# foxcar-control-board-v1.net
KiCad netlist of a schematic drawn in EAGLE
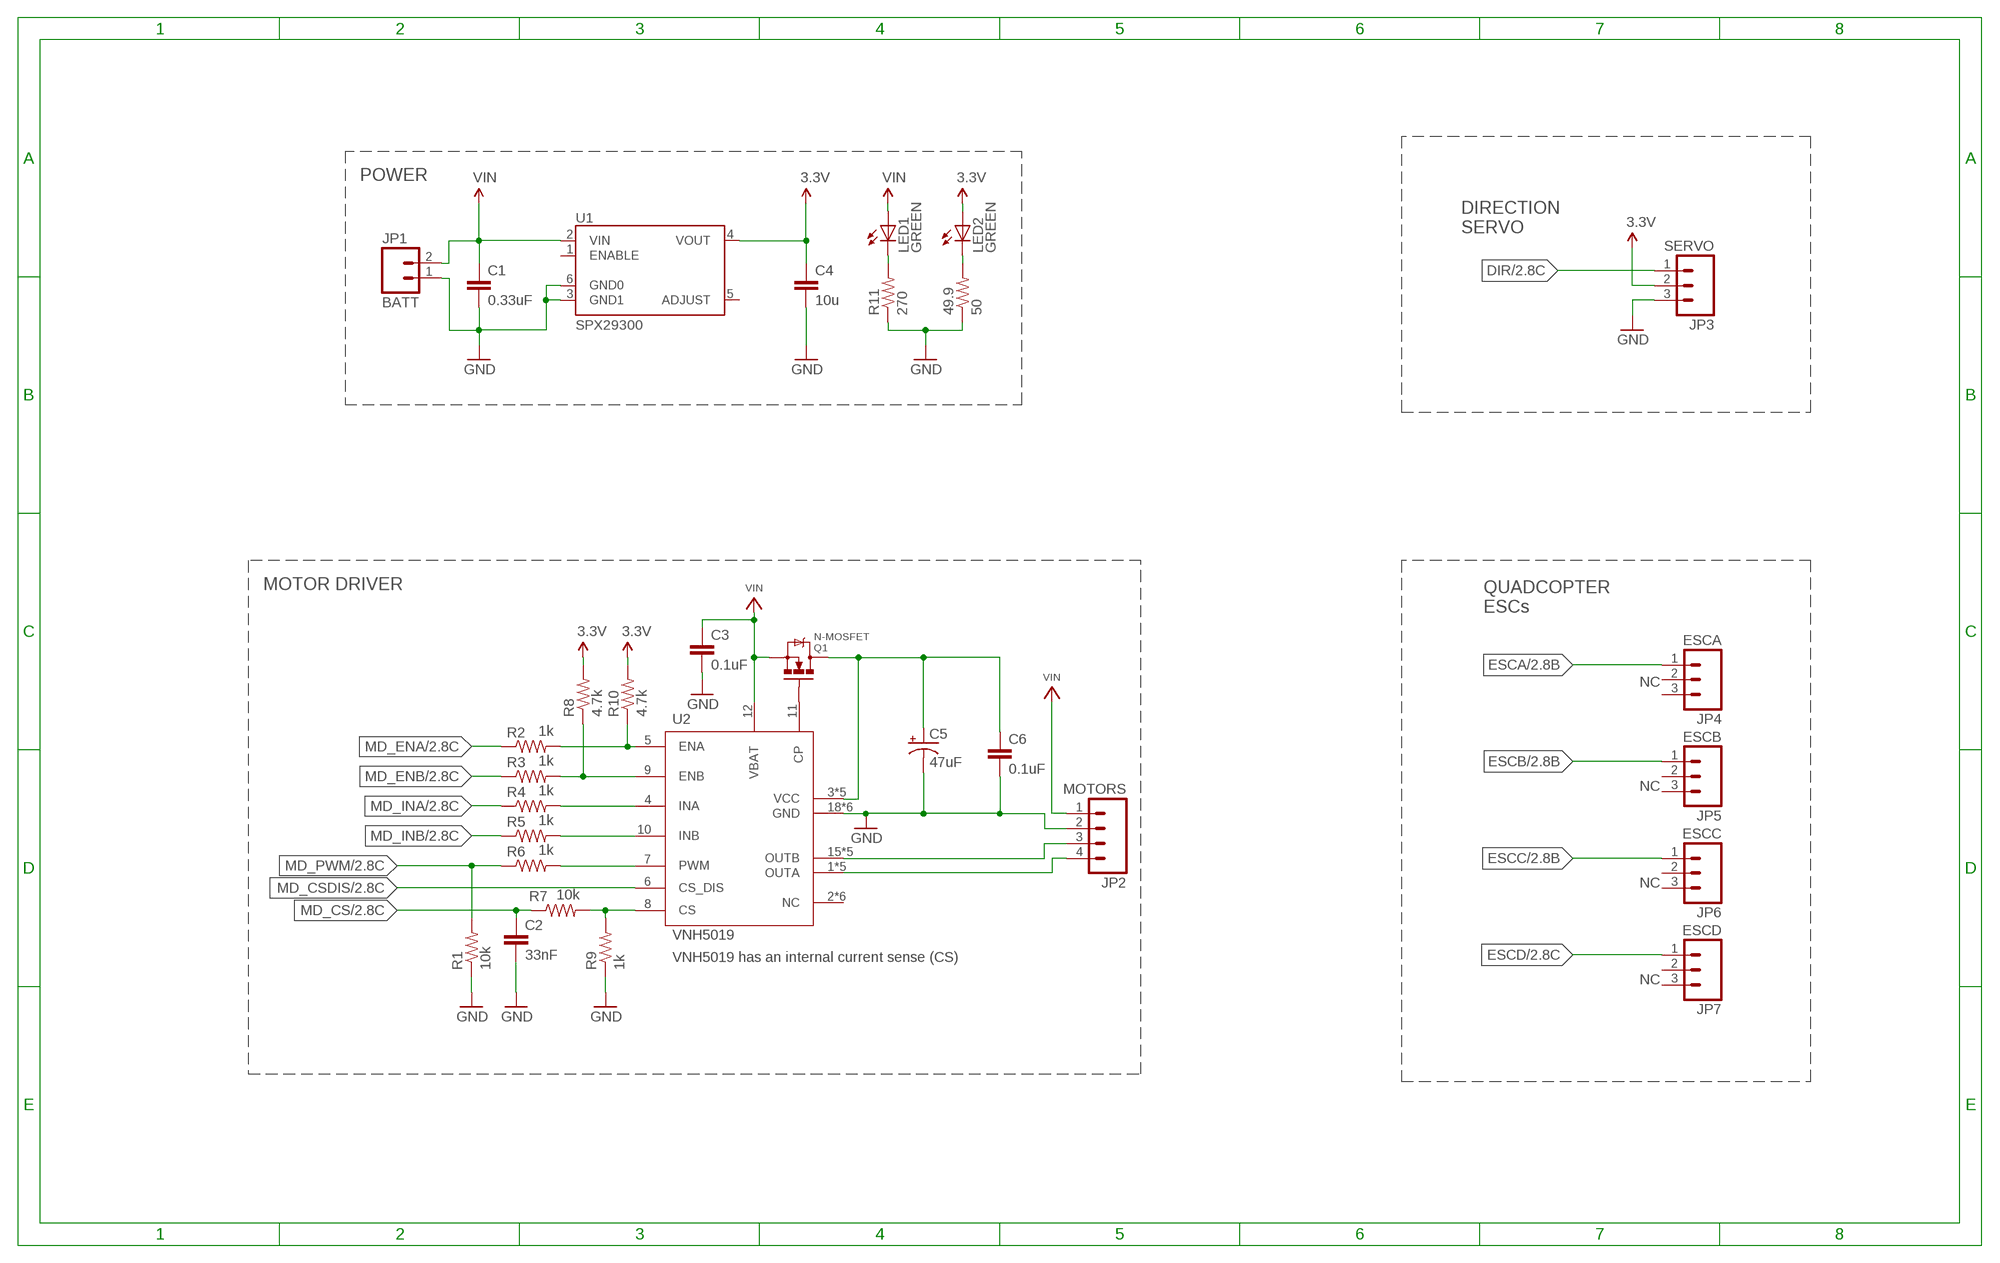
[diagram p0: schematic, sheet 1]
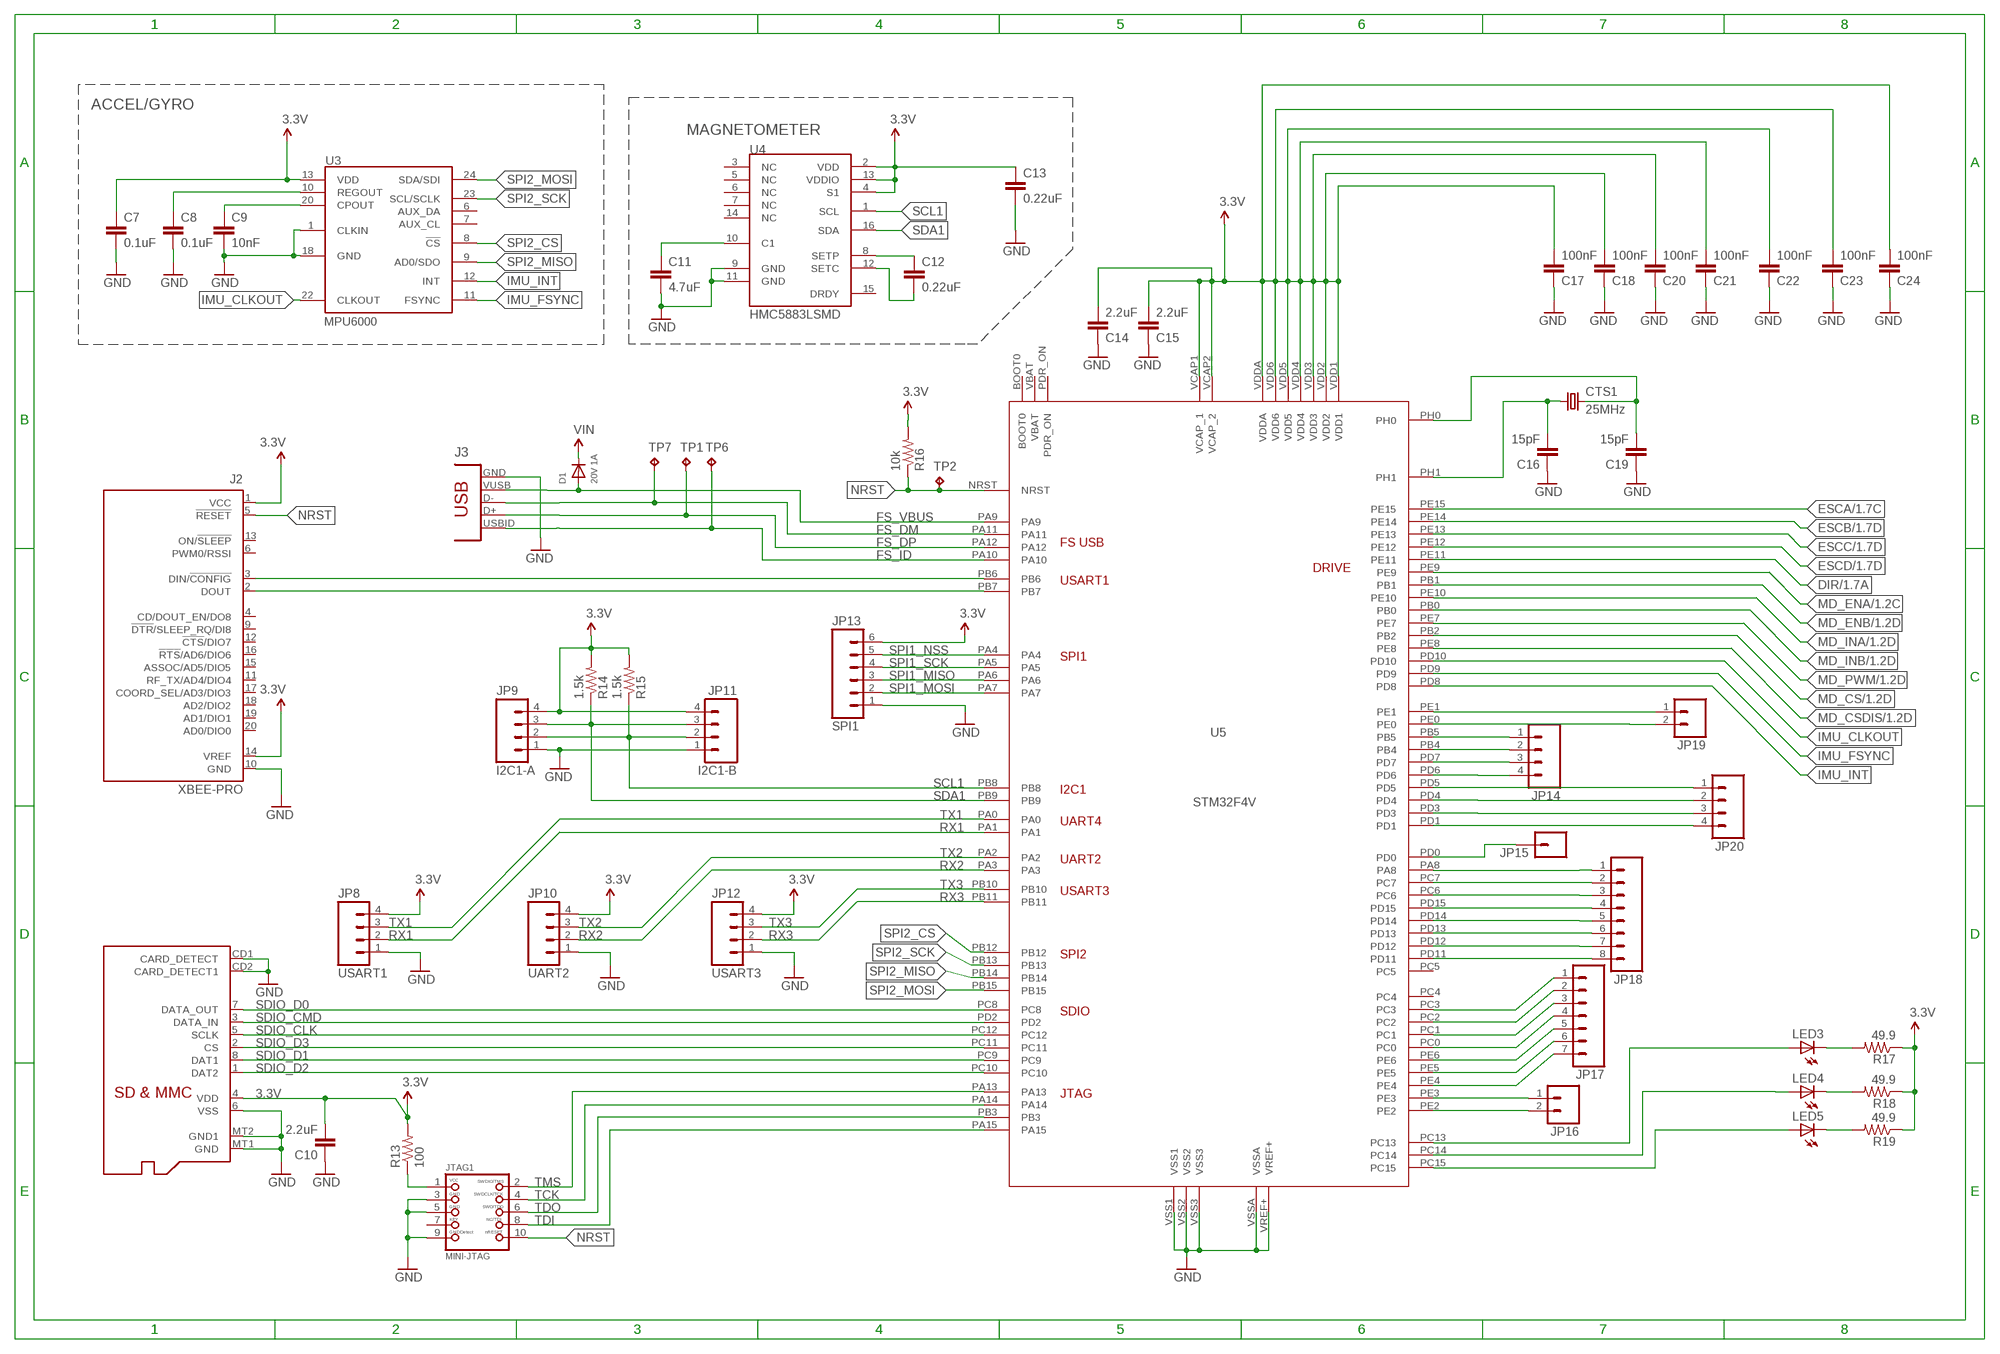
[diagram p1: schematic, sheet 2]

(export (version "E")
  (design (tool "Eeschema 10.0.6"))
  (components
    (comp (ref "C7")
      (value "0.1uF")
      (footprint "eagle-import:0402-CAP")
      (libsource (lib "eagle-import") (part "CAP0402-CAP"))
    )
    (comp (ref "C8")
      (value "0.1uF")
      (footprint "eagle-import:0402-CAP")
      (libsource (lib "eagle-import") (part "CAP0402-CAP"))
    )
    (comp (ref "C9")
      (value "10nF")
      (footprint "eagle-import:0402-CAP")
      (libsource (lib "eagle-import") (part "CAP0402-CAP"))
    )
    (comp (ref "C10")
      (value "2.2uF")
      (footprint "eagle-import:0402-CAP")
      (libsource (lib "eagle-import") (part "CAP0402-CAP"))
    )
    (comp (ref "C11")
      (value "4.7uF")
      (footprint "eagle-import:0402-CAP")
      (libsource (lib "eagle-import") (part "CAP0402-CAP"))
    )
    (comp (ref "C12")
      (value "0.22uF")
      (footprint "eagle-import:0402-CAP")
      (libsource (lib "eagle-import") (part "CAP0402-CAP"))
    )
    (comp (ref "C13")
      (value "0.22uF")
      (footprint "eagle-import:0402-CAP")
      (libsource (lib "eagle-import") (part "CAP0402-CAP"))
    )
    (comp (ref "C14")
      (value "2.2uF")
      (footprint "eagle-import:0402-CAP")
      (libsource (lib "eagle-import") (part "CAP0402-CAP"))
    )
    (comp (ref "C15")
      (value "2.2uF")
      (footprint "eagle-import:0402-CAP")
      (libsource (lib "eagle-import") (part "CAP0402-CAP"))
    )
    (comp (ref "C16")
      (value "15pF")
      (footprint "eagle-import:0402-CAP")
      (libsource (lib "eagle-import") (part "CAP0402-CAP"))
    )
    (comp (ref "C17")
      (value "100nF")
      (footprint "eagle-import:0402-CAP")
      (libsource (lib "eagle-import") (part "CAP0402-CAP"))
    )
    (comp (ref "C18")
      (value "100nF")
      (footprint "eagle-import:0402-CAP")
      (libsource (lib "eagle-import") (part "CAP0402-CAP"))
    )
    (comp (ref "C19")
      (value "15pF")
      (footprint "eagle-import:0402-CAP")
      (libsource (lib "eagle-import") (part "CAP0402-CAP"))
    )
    (comp (ref "C20")
      (value "100nF")
      (footprint "eagle-import:0402-CAP")
      (libsource (lib "eagle-import") (part "CAP0402-CAP"))
    )
    (comp (ref "C21")
      (value "100nF")
      (footprint "eagle-import:0402-CAP")
      (libsource (lib "eagle-import") (part "CAP0402-CAP"))
    )
    (comp (ref "C22")
      (value "100nF")
      (footprint "eagle-import:0402-CAP")
      (libsource (lib "eagle-import") (part "CAP0402-CAP"))
    )
    (comp (ref "C23")
      (value "100nF")
      (footprint "eagle-import:0402-CAP")
      (libsource (lib "eagle-import") (part "CAP0402-CAP"))
    )
    (comp (ref "C24")
      (value "100nF")
      (footprint "eagle-import:0402-CAP")
      (libsource (lib "eagle-import") (part "CAP0402-CAP"))
    )
    (comp (ref "CTS1")
      (value "25MHz")
      (footprint "eagle-import:CTS406")
      (libsource (lib "eagle-import") (part "CRYSTALCTS406"))
    )
    (comp (ref "D1")
      (value "20V 1A")
      (footprint "eagle-import:SMADIODE")
      (libsource (lib "eagle-import") (part "DIODESMA"))
    )
    (comp (ref "J1")
      (value "MICROSD")
      (footprint "eagle-import:MICROSD")
      (libsource (lib "eagle-import") (part "MICROSD"))
    )
    (comp (ref "J2")
      (value "XBEE-PRO")
      (footprint "eagle-import:XBEE-PRO")
      (fields (field (name "MPN") "XBP24-AWI-001"))
      (libsource (lib "eagle-import") (part "XBEE-PRO"))
    )
    (comp (ref "J3")
      (value "CON-USB-F-MICRO-B")
      (footprint "eagle-import:CONN_USB_MICRO-B")
      (libsource (lib "eagle-import") (part "CON-USB-F-MICRO-B"))
    )
    (comp (ref "JP8")
      (value "USART1")
      (footprint "eagle-import:1X04_LOCK_LONGPADS")
      (libsource (lib "eagle-import") (part "M04LOCK_LONGPADS"))
    )
    (comp (ref "JP9")
      (value "I2C1-A")
      (footprint "eagle-import:1X04_LOCK_LONGPADS")
      (libsource (lib "eagle-import") (part "M04LOCK_LONGPADS"))
    )
    (comp (ref "JP10")
      (value "UART2")
      (footprint "eagle-import:1X04_LOCK_LONGPADS")
      (libsource (lib "eagle-import") (part "M04LOCK_LONGPADS"))
    )
    (comp (ref "JP11")
      (value "I2C1-B")
      (footprint "eagle-import:1X04_LOCK_LONGPADS")
      (libsource (lib "eagle-import") (part "M04LOCK_LONGPADS"))
    )
    (comp (ref "JP12")
      (value "USART3")
      (footprint "eagle-import:1X04_LOCK_LONGPADS")
      (libsource (lib "eagle-import") (part "M04LOCK_LONGPADS"))
    )
    (comp (ref "JP13")
      (value "SPI1")
      (footprint "eagle-import:1X06_LOCK_LONGPADS")
      (libsource (lib "eagle-import") (part "M06LOCK_LONGPADS"))
    )
    (comp (ref "JP14")
      (value "M04LOCK")
      (footprint "eagle-import:1X04_LOCK")
      (libsource (lib "eagle-import") (part "M04LOCK"))
    )
    (comp (ref "JP15")
      (value "M01PTH")
      (footprint "eagle-import:1X01")
      (libsource (lib "eagle-import") (part "M01PTH"))
    )
    (comp (ref "JP16")
      (value "M02LOCK_LONGPADS")
      (footprint "eagle-import:1X02_LOCK_LONGPADS")
      (libsource (lib "eagle-import") (part "M02LOCK_LONGPADS"))
    )
    (comp (ref "JP17")
      (value "M07LOCK")
      (footprint "eagle-import:1X07_LOCK")
      (libsource (lib "eagle-import") (part "M07LOCK"))
    )
    (comp (ref "JP18")
      (value "M08LOCK_LONGPADS")
      (footprint "eagle-import:1X08_LOCK_LONGPADS")
      (libsource (lib "eagle-import") (part "M08LOCK_LONGPADS"))
    )
    (comp (ref "JP19")
      (value "M02LOCK")
      (footprint "eagle-import:1X02_LOCK")
      (libsource (lib "eagle-import") (part "M02LOCK"))
    )
    (comp (ref "JP20")
      (value "M04LOCK")
      (footprint "eagle-import:1X04_LOCK")
      (libsource (lib "eagle-import") (part "M04LOCK"))
    )
    (comp (ref "JTAG1")
      (value "MINI-JTAG")
      (footprint "eagle-import:2X05_1.27MM_SMT")
      (libsource (lib "eagle-import") (part "JTAG-CORTEXM3"))
    )
    (comp (ref "LED3")
      (value "LEDCHIPLED_0603")
      (footprint "eagle-import:CHIPLED_0603")
      (libsource (lib "eagle-import") (part "LEDCHIPLED_0603"))
    )
    (comp (ref "LED4")
      (value "LEDCHIPLED_0603")
      (footprint "eagle-import:CHIPLED_0603")
      (libsource (lib "eagle-import") (part "LEDCHIPLED_0603"))
    )
    (comp (ref "LED5")
      (value "LEDCHIPLED_0603")
      (footprint "eagle-import:CHIPLED_0603")
      (libsource (lib "eagle-import") (part "LEDCHIPLED_0603"))
    )
    (comp (ref "R13")
      (value "100")
      (footprint "eagle-import:0402-RES")
      (libsource (lib "eagle-import") (part "RESISTOR0402-RES"))
    )
    (comp (ref "R14")
      (value "1.5k")
      (footprint "eagle-import:0402-RES")
      (libsource (lib "eagle-import") (part "RESISTOR0402-RES"))
    )
    (comp (ref "R15")
      (value "1.5k")
      (footprint "eagle-import:0402-RES")
      (libsource (lib "eagle-import") (part "RESISTOR0402-RES"))
    )
    (comp (ref "R16")
      (value "10k")
      (footprint "eagle-import:0402-RES")
      (libsource (lib "eagle-import") (part "RESISTOR0402-RES"))
    )
    (comp (ref "R17")
      (value "49.9")
      (footprint "eagle-import:0402-RES")
      (libsource (lib "eagle-import") (part "RESISTOR0402-RES"))
    )
    (comp (ref "R18")
      (value "49.9")
      (footprint "eagle-import:0402-RES")
      (libsource (lib "eagle-import") (part "RESISTOR0402-RES"))
    )
    (comp (ref "R19")
      (value "49.9")
      (footprint "eagle-import:0402-RES")
      (libsource (lib "eagle-import") (part "RESISTOR0402-RES"))
    )
    (comp (ref "TP1")
      (value "TPTP06R")
      (footprint "eagle-import:TP06R")
      (libsource (lib "eagle-import") (part "TPTP06R"))
    )
    (comp (ref "TP2")
      (value "TPTP06R")
      (footprint "eagle-import:TP06R")
      (libsource (lib "eagle-import") (part "TPTP06R"))
    )
    (comp (ref "TP6")
      (value "TPTP06R")
      (footprint "eagle-import:TP06R")
      (libsource (lib "eagle-import") (part "TPTP06R"))
    )
    (comp (ref "TP7")
      (value "TPTP06R")
      (footprint "eagle-import:TP06R")
      (libsource (lib "eagle-import") (part "TPTP06R"))
    )
    (comp (ref "U3")
      (value "MPU6000")
      (footprint "eagle-import:QFN.24.4X4")
      (libsource (lib "eagle-import") (part "MPU-6000"))
    )
    (comp (ref "U4")
      (value "HMC5883LSMD")
      (footprint "eagle-import:16LPCC")
      (libsource (lib "eagle-import") (part "HMC5883LSMD"))
    )
    (comp (ref "U5")
      (value "STM32F4V")
      (footprint "eagle-import:LQFP100")
      (libsource (lib "eagle-import") (part "STM32F4V_100PIN_FOXCAR"))
    )
    (comp (ref "49.9")
      (value "50")
      (footprint "eagle-import:0402-RES")
      (libsource (lib "eagle-import") (part "RESISTOR0402-RES"))
    )
    (comp (ref "C1")
      (value "0.33uF")
      (footprint "eagle-import:0402-CAP")
      (libsource (lib "eagle-import") (part "CAP0402-CAP"))
    )
    (comp (ref "C2")
      (value "33nF")
      (footprint "eagle-import:0402-CAP")
      (libsource (lib "eagle-import") (part "CAP0402-CAP"))
    )
    (comp (ref "C3")
      (value "0.1uF")
      (footprint "eagle-import:0402-CAP")
      (libsource (lib "eagle-import") (part "CAP0402-CAP"))
    )
    (comp (ref "C4")
      (value "10u")
      (footprint "eagle-import:0603-CAP")
      (libsource (lib "eagle-import") (part "CAP0603-CAP"))
    )
    (comp (ref "C5")
      (value "47uF")
      (footprint "eagle-import:PANASONIC_D")
      (libsource (lib "eagle-import") (part "CAP_POLD"))
    )
    (comp (ref "C6")
      (value "0.1uF")
      (footprint "eagle-import:0402-CAP")
      (libsource (lib "eagle-import") (part "CAP0402-CAP"))
    )
    (comp (ref "JP1")
      (value "BATT")
      (footprint "eagle-import:SCREWTERMINAL-3.5MM-2_LOCK")
      (libsource (lib "eagle-import") (part "M023.5MM_LOCK"))
    )
    (comp (ref "JP2")
      (value "MOTORS")
      (footprint "eagle-import:SCREWTERMINAL-3.5MM-4_LOCK")
      (libsource (lib "eagle-import") (part "M04SCREW_LOCK"))
    )
    (comp (ref "JP3")
      (value "SERVO")
      (footprint "eagle-import:1X03_LOCK_LONGPADS")
      (libsource (lib "eagle-import") (part "M03LOCK_LONGPADS"))
    )
    (comp (ref "JP4")
      (value "ESCA")
      (footprint "eagle-import:1X03_LOCK_LONGPADS")
      (libsource (lib "eagle-import") (part "M03LOCK_LONGPADS"))
    )
    (comp (ref "JP5")
      (value "ESCB")
      (footprint "eagle-import:1X03_LOCK_LONGPADS")
      (libsource (lib "eagle-import") (part "M03LOCK_LONGPADS"))
    )
    (comp (ref "JP6")
      (value "ESCC")
      (footprint "eagle-import:1X03_LOCK_LONGPADS")
      (libsource (lib "eagle-import") (part "M03LOCK_LONGPADS"))
    )
    (comp (ref "JP7")
      (value "ESCD")
      (footprint "eagle-import:1X03_LOCK_LONGPADS")
      (libsource (lib "eagle-import") (part "M03LOCK_LONGPADS"))
    )
    (comp (ref "LED1")
      (value "GREEN")
      (footprint "eagle-import:CHIPLED_0603")
      (libsource (lib "eagle-import") (part "LEDCHIPLED_0603"))
    )
    (comp (ref "LED2")
      (value "GREEN")
      (footprint "eagle-import:CHIPLED_0603")
      (libsource (lib "eagle-import") (part "LEDCHIPLED_0603"))
    )
    (comp (ref "Q1")
      (value "N-MOSFET")
      (footprint "eagle-import:TO220V")
      (libsource (lib "eagle-import") (part "MOSFET-NCHANNELPTH2"))
    )
    (comp (ref "R1")
      (value "10k")
      (footprint "eagle-import:0603-RES")
      (libsource (lib "eagle-import") (part "RESISTOR0603-RES"))
    )
    (comp (ref "R2")
      (value "1k")
      (footprint "eagle-import:0402-RES")
      (libsource (lib "eagle-import") (part "RESISTOR0402-RES"))
    )
    (comp (ref "R3")
      (value "1k")
      (footprint "eagle-import:0402-RES")
      (libsource (lib "eagle-import") (part "RESISTOR0402-RES"))
    )
    (comp (ref "R4")
      (value "1k")
      (footprint "eagle-import:0402-RES")
      (libsource (lib "eagle-import") (part "RESISTOR0402-RES"))
    )
    (comp (ref "R5")
      (value "1k")
      (footprint "eagle-import:0402-RES")
      (libsource (lib "eagle-import") (part "RESISTOR0402-RES"))
    )
    (comp (ref "R6")
      (value "1k")
      (footprint "eagle-import:0402-RES")
      (libsource (lib "eagle-import") (part "RESISTOR0402-RES"))
    )
    (comp (ref "R7")
      (value "10k")
      (footprint "eagle-import:0402-RES")
      (libsource (lib "eagle-import") (part "RESISTOR0402-RES"))
    )
    (comp (ref "R8")
      (value "4.7k")
      (footprint "eagle-import:0402-RES")
      (libsource (lib "eagle-import") (part "RESISTOR0402-RES"))
    )
    (comp (ref "R9")
      (value "1k")
      (footprint "eagle-import:0402-RES")
      (libsource (lib "eagle-import") (part "RESISTOR0402-RES"))
    )
    (comp (ref "R10")
      (value "4.7k")
      (footprint "eagle-import:0402-RES")
      (libsource (lib "eagle-import") (part "RESISTOR0402-RES"))
    )
    (comp (ref "R11")
      (value "270")
      (footprint "eagle-import:0603-RES")
      (libsource (lib "eagle-import") (part "RESISTOR0603-RES"))
    )
    (comp (ref "U1")
      (value "SPX29300")
      (footprint "eagle-import:TO263-5")
      (libsource (lib "eagle-import") (part "VREG_TO263-5"))
    )
    (comp (ref "U2")
      (value "VNH5019")
      (footprint "eagle-import:MULTIPOWERSO-30")
      (libsource (lib "eagle-import") (part "VNH5019"))
    )
  )
  (nets
    (net (code "1") (name "3.3V") (class "Default")
      (node (ref "C10") (pin "2") (pinfunction "2_2") (pintype "passive"))
      (node (ref "C13") (pin "1") (pinfunction "1_1") (pintype "passive"))
      (node (ref "C14") (pin "2") (pinfunction "2_2") (pintype "passive"))
      (node (ref "C15") (pin "2") (pinfunction "2_2") (pintype "passive"))
      (node (ref "C17") (pin "2") (pinfunction "2_2") (pintype "passive"))
      (node (ref "C18") (pin "2") (pinfunction "2_2") (pintype "passive"))
      (node (ref "C20") (pin "2") (pinfunction "2_2") (pintype "passive"))
      (node (ref "C21") (pin "2") (pinfunction "2_2") (pintype "passive"))
      (node (ref "C22") (pin "2") (pinfunction "2_2") (pintype "passive"))
      (node (ref "C23") (pin "2") (pinfunction "2_2") (pintype "passive"))
      (node (ref "C24") (pin "2") (pinfunction "2_2") (pintype "passive"))
      (node (ref "C4") (pin "1") (pinfunction "1_1") (pintype "passive"))
      (node (ref "C7") (pin "1") (pinfunction "1_1") (pintype "passive"))
      (node (ref "J1") (pin "4") (pinfunction "VDD_4") (pintype "power_in"))
      (node (ref "J2") (pin "1") (pinfunction "VCC_1") (pintype "power_in"))
      (node (ref "J2") (pin "14") (pinfunction "VREF_14") (pintype "input"))
      (node (ref "JP10") (pin "4") (pinfunction "4_4") (pintype "passive"))
      (node (ref "JP11") (pin "4") (pinfunction "4_4") (pintype "passive"))
      (node (ref "JP12") (pin "4") (pinfunction "4_4") (pintype "passive"))
      (node (ref "JP13") (pin "6") (pinfunction "6_6") (pintype "passive"))
      (node (ref "JP3") (pin "2") (pinfunction "2_2") (pintype "passive"))
      (node (ref "JP8") (pin "4") (pinfunction "4_4") (pintype "passive"))
      (node (ref "JP9") (pin "4") (pinfunction "4_4") (pintype "passive"))
      (node (ref "LED2") (pin "A") (pinfunction "A_A") (pintype "passive"))
      (node (ref "R10") (pin "2") (pinfunction "2_2") (pintype "passive"))
      (node (ref "R13") (pin "2") (pinfunction "2_2") (pintype "passive"))
      (node (ref "R14") (pin "2") (pinfunction "2_2") (pintype "passive"))
      (node (ref "R15") (pin "2") (pinfunction "2_2") (pintype "passive"))
      (node (ref "R16") (pin "2") (pinfunction "2_2") (pintype "passive"))
      (node (ref "R17") (pin "1") (pinfunction "1_1") (pintype "passive"))
      (node (ref "R18") (pin "1") (pinfunction "1_1") (pintype "passive"))
      (node (ref "R19") (pin "1") (pinfunction "1_1") (pintype "passive"))
      (node (ref "R8") (pin "2") (pinfunction "2_2") (pintype "passive"))
      (node (ref "U1") (pin "4") (pinfunction "VOUT_4") (pintype "bidirectional"))
      (node (ref "U3") (pin "13") (pinfunction "VDD_13") (pintype "bidirectional"))
      (node (ref "U4") (pin "13") (pinfunction "VDDIO_13") (pintype "bidirectional"))
      (node (ref "U4") (pin "2") (pinfunction "VDD_2") (pintype "bidirectional"))
      (node (ref "U4") (pin "4") (pinfunction "S1_4") (pintype "bidirectional"))
      (node (ref "U5") (pin "VCAP1") (pinfunction "VCAP_1_VCAP1") (pintype "bidirectional"))
      (node (ref "U5") (pin "VCAP2") (pinfunction "VCAP_2_VCAP2") (pintype "bidirectional"))
      (node (ref "U5") (pin "VDD1") (pinfunction "VDD1_VDD1") (pintype "bidirectional"))
      (node (ref "U5") (pin "VDD2") (pinfunction "VDD2_VDD2") (pintype "bidirectional"))
      (node (ref "U5") (pin "VDD3") (pinfunction "VDD3_VDD3") (pintype "bidirectional"))
      (node (ref "U5") (pin "VDD4") (pinfunction "VDD4_VDD4") (pintype "bidirectional"))
      (node (ref "U5") (pin "VDD5") (pinfunction "VDD5_VDD5") (pintype "bidirectional"))
      (node (ref "U5") (pin "VDD6") (pinfunction "VDD6_VDD6") (pintype "bidirectional"))
      (node (ref "U5") (pin "VDDA") (pinfunction "VDDA_VDDA") (pintype "bidirectional"))
    )
    (net (code "2") (name "DIR") (class "Default")
      (node (ref "JP3") (pin "1") (pinfunction "1_1") (pintype "passive"))
      (node (ref "U5") (pin "PE11") (pinfunction "PE11_PE11") (pintype "bidirectional"))
    )
    (net (code "3") (name "ESCA") (class "Default")
      (node (ref "JP4") (pin "1") (pinfunction "1_1") (pintype "passive"))
      (node (ref "U5") (pin "PE15") (pinfunction "PE15_PE15") (pintype "bidirectional"))
    )
    (net (code "4") (name "ESCB") (class "Default")
      (node (ref "JP5") (pin "1") (pinfunction "1_1") (pintype "passive"))
      (node (ref "U5") (pin "PE14") (pinfunction "PE14_PE14") (pintype "bidirectional"))
    )
    (net (code "5") (name "ESCC") (class "Default")
      (node (ref "JP6") (pin "1") (pinfunction "1_1") (pintype "passive"))
      (node (ref "U5") (pin "PE13") (pinfunction "PE13_PE13") (pintype "bidirectional"))
    )
    (net (code "6") (name "ESCD") (class "Default")
      (node (ref "JP7") (pin "1") (pinfunction "1_1") (pintype "passive"))
      (node (ref "U5") (pin "PE12") (pinfunction "PE12_PE12") (pintype "bidirectional"))
    )
    (net (code "7") (name "FS_DM") (class "Default")
      (node (ref "J3") (pin "P2") (pinfunction "D-_P2") (pintype "bidirectional"))
      (node (ref "TP7") (pin "TP") (pinfunction "TP_TP") (pintype "input"))
      (node (ref "U5") (pin "PA11") (pinfunction "PA11_PA11") (pintype "bidirectional"))
    )
    (net (code "8") (name "FS_DP") (class "Default")
      (node (ref "J3") (pin "P3") (pinfunction "D+_P3") (pintype "bidirectional"))
      (node (ref "TP1") (pin "TP") (pinfunction "TP_TP") (pintype "input"))
      (node (ref "U5") (pin "PA12") (pinfunction "PA12_PA12") (pintype "bidirectional"))
    )
    (net (code "9") (name "FS_ID") (class "Default")
      (node (ref "J3") (pin "P4") (pinfunction "USBID_P4") (pintype "bidirectional"))
      (node (ref "TP6") (pin "TP") (pinfunction "TP_TP") (pintype "input"))
      (node (ref "U5") (pin "PA10") (pinfunction "PA10_PA10") (pintype "bidirectional"))
    )
    (net (code "10") (name "FS_VBUS") (class "Default")
      (node (ref "D1") (pin "A") (pinfunction "A_A") (pintype "passive"))
      (node (ref "J3") (pin "P1") (pinfunction "VUSB_P1") (pintype "bidirectional"))
      (node (ref "U5") (pin "PA9") (pinfunction "PA9_PA9") (pintype "bidirectional"))
    )
    (net (code "11") (name "GND") (class "Default")
      (node (ref "49.9") (pin "1") (pinfunction "1_1") (pintype "passive"))
      (node (ref "C1") (pin "2") (pinfunction "2_2") (pintype "passive"))
      (node (ref "C10") (pin "1") (pinfunction "1_1") (pintype "passive"))
      (node (ref "C11") (pin "2") (pinfunction "2_2") (pintype "passive"))
      (node (ref "C13") (pin "2") (pinfunction "2_2") (pintype "passive"))
      (node (ref "C14") (pin "1") (pinfunction "1_1") (pintype "passive"))
      (node (ref "C15") (pin "1") (pinfunction "1_1") (pintype "passive"))
      (node (ref "C16") (pin "1") (pinfunction "1_1") (pintype "passive"))
      (node (ref "C17") (pin "1") (pinfunction "1_1") (pintype "passive"))
      (node (ref "C18") (pin "1") (pinfunction "1_1") (pintype "passive"))
      (node (ref "C19") (pin "1") (pinfunction "1_1") (pintype "passive"))
      (node (ref "C2") (pin "2") (pinfunction "2_2") (pintype "passive"))
      (node (ref "C20") (pin "1") (pinfunction "1_1") (pintype "passive"))
      (node (ref "C21") (pin "1") (pinfunction "1_1") (pintype "passive"))
      (node (ref "C22") (pin "1") (pinfunction "1_1") (pintype "passive"))
      (node (ref "C23") (pin "1") (pinfunction "1_1") (pintype "passive"))
      (node (ref "C24") (pin "1") (pinfunction "1_1") (pintype "passive"))
      (node (ref "C3") (pin "2") (pinfunction "2_2") (pintype "passive"))
      (node (ref "C4") (pin "2") (pinfunction "2_2") (pintype "passive"))
      (node (ref "C5") (pin "-") (pinfunction "-_-") (pintype "passive"))
      (node (ref "C6") (pin "2") (pinfunction "2_2") (pintype "passive"))
      (node (ref "C7") (pin "2") (pinfunction "2_2") (pintype "passive"))
      (node (ref "C8") (pin "2") (pinfunction "2_2") (pintype "passive"))
      (node (ref "C9") (pin "2") (pinfunction "2_2") (pintype "passive"))
      (node (ref "J1") (pin "6") (pinfunction "VSS_6") (pintype "power_in"))
      (node (ref "J1") (pin "CD1") (pinfunction "CARD_DETECT_CD1") (pintype "passive"))
      (node (ref "J1") (pin "CD2") (pinfunction "CARD_DETECT1_CD2") (pintype "passive"))
      (node (ref "J1") (pin "MT1") (pinfunction "GND_MT1") (pintype "power_in"))
      (node (ref "J1") (pin "MT2") (pinfunction "GND1_MT2") (pintype "power_in"))
      (node (ref "J2") (pin "10") (pinfunction "GND_10") (pintype "power_in"))
      (node (ref "J3") (pin "P5") (pinfunction "GND_P5") (pintype "bidirectional"))
      (node (ref "JP1") (pin "1") (pinfunction "1_1") (pintype "passive"))
      (node (ref "JP10") (pin "1") (pinfunction "1_1") (pintype "passive"))
      (node (ref "JP11") (pin "1") (pinfunction "1_1") (pintype "passive"))
      (node (ref "JP12") (pin "1") (pinfunction "1_1") (pintype "passive"))
      (node (ref "JP13") (pin "1") (pinfunction "1_1") (pintype "passive"))
      (node (ref "JP2") (pin "2") (pinfunction "2_2") (pintype "passive"))
      (node (ref "JP3") (pin "3") (pinfunction "3_3") (pintype "passive"))
      (node (ref "JP8") (pin "1") (pinfunction "1_1") (pintype "passive"))
      (node (ref "JP9") (pin "1") (pinfunction "1_1") (pintype "passive"))
      (node (ref "JTAG1") (pin "3") (pinfunction "3_3") (pintype "passive"))
      (node (ref "JTAG1") (pin "5") (pinfunction "5_5") (pintype "passive"))
      (node (ref "JTAG1") (pin "9") (pinfunction "9_9") (pintype "passive"))
      (node (ref "R1") (pin "1") (pinfunction "1_1") (pintype "passive"))
      (node (ref "R11") (pin "1") (pinfunction "1_1") (pintype "passive"))
      (node (ref "R9") (pin "1") (pinfunction "1_1") (pintype "passive"))
      (node (ref "U1") (pin "3") (pinfunction "GND1_3") (pintype "bidirectional"))
      (node (ref "U1") (pin "6") (pinfunction "GND0_6") (pintype "bidirectional"))
      (node (ref "U2") (pin "18") (pinfunction "GND_18") (pintype "power_in"))
      (node (ref "U2") (pin "19") (pinfunction "GND_19") (pintype "power_in"))
      (node (ref "U2") (pin "20") (pinfunction "GND_20") (pintype "power_in"))
      (node (ref "U2") (pin "26") (pinfunction "GND_26") (pintype "power_in"))
      (node (ref "U2") (pin "27") (pinfunction "GND_27") (pintype "power_in"))
      (node (ref "U2") (pin "28") (pinfunction "GND_28") (pintype "power_in"))
      (node (ref "U3") (pin "1") (pinfunction "CLKIN_1") (pintype "bidirectional"))
      (node (ref "U3") (pin "18") (pinfunction "GND_18") (pintype "bidirectional"))
      (node (ref "U4") (pin "11") (pinfunction "GND_11") (pintype "bidirectional"))
      (node (ref "U4") (pin "9") (pinfunction "GND_9") (pintype "bidirectional"))
      (node (ref "U5") (pin "VREF+") (pinfunction "VREF+_VREF+") (pintype "bidirectional"))
      (node (ref "U5") (pin "VSS1") (pinfunction "VSS1_VSS1") (pintype "bidirectional"))
      (node (ref "U5") (pin "VSS2") (pinfunction "VSS2_VSS2") (pintype "bidirectional"))
      (node (ref "U5") (pin "VSS3") (pinfunction "VSS3_VSS3") (pintype "bidirectional"))
      (node (ref "U5") (pin "VSSA") (pinfunction "VSSA_VSSA") (pintype "bidirectional"))
    )
    (net (code "12") (name "IMU_CLKOUT") (class "Default")
      (node (ref "U3") (pin "22") (pinfunction "CLKOUT_22") (pintype "bidirectional"))
      (node (ref "U5") (pin "PD10") (pinfunction "PD10_PD10") (pintype "bidirectional"))
    )
    (net (code "13") (name "IMU_FSYNC") (class "Default")
      (node (ref "U3") (pin "11") (pinfunction "FSYNC_11") (pintype "bidirectional"))
      (node (ref "U5") (pin "PD9") (pinfunction "PD9_PD9") (pintype "bidirectional"))
    )
    (net (code "14") (name "IMU_INT") (class "Default")
      (node (ref "U3") (pin "12") (pinfunction "INT_12") (pintype "bidirectional"))
      (node (ref "U5") (pin "PD8") (pinfunction "PD8_PD8") (pintype "bidirectional"))
    )
    (net (code "15") (name "MD_CS") (class "Default")
      (node (ref "C2") (pin "1") (pinfunction "1_1") (pintype "passive"))
      (node (ref "R7") (pin "1") (pinfunction "1_1") (pintype "passive"))
      (node (ref "U5") (pin "PB2") (pinfunction "PB2_PB2") (pintype "bidirectional"))
    )
    (net (code "16") (name "MD_CSDIS") (class "Default")
      (node (ref "U2") (pin "6") (pinfunction "CS_DIS_6") (pintype "bidirectional"))
      (node (ref "U5") (pin "PE8") (pinfunction "PE8_PE8") (pintype "bidirectional"))
    )
    (net (code "17") (name "MD_ENA") (class "Default")
      (node (ref "R2") (pin "1") (pinfunction "1_1") (pintype "passive"))
      (node (ref "U5") (pin "PE9") (pinfunction "PE9_PE9") (pintype "bidirectional"))
    )
    (net (code "18") (name "MD_ENB") (class "Default")
      (node (ref "R3") (pin "1") (pinfunction "1_1") (pintype "passive"))
      (node (ref "U5") (pin "PB1") (pinfunction "PB1_PB1") (pintype "bidirectional"))
    )
    (net (code "19") (name "MD_INA") (class "Default")
      (node (ref "R4") (pin "1") (pinfunction "1_1") (pintype "passive"))
      (node (ref "U5") (pin "PE10") (pinfunction "PE10_PE10") (pintype "bidirectional"))
    )
    (net (code "20") (name "MD_INB") (class "Default")
      (node (ref "R5") (pin "1") (pinfunction "1_1") (pintype "passive"))
      (node (ref "U5") (pin "PB0") (pinfunction "PB0_PB0") (pintype "bidirectional"))
    )
    (net (code "21") (name "MD_PWM") (class "Default")
      (node (ref "R1") (pin "2") (pinfunction "2_2") (pintype "passive"))
      (node (ref "R6") (pin "1") (pinfunction "1_1") (pintype "passive"))
      (node (ref "U5") (pin "PE7") (pinfunction "PE7_PE7") (pintype "bidirectional"))
    )
    (net (code "22") (name "NRST") (class "Default")
      (node (ref "J2") (pin "5") (pinfunction "~{RESET}_5") (pintype "input"))
      (node (ref "JTAG1") (pin "10") (pinfunction "10_10") (pintype "passive"))
      (node (ref "R16") (pin "1") (pinfunction "1_1") (pintype "passive"))
      (node (ref "TP2") (pin "TP") (pinfunction "TP_TP") (pintype "input"))
      (node (ref "U5") (pin "NRST") (pinfunction "NRST_NRST") (pintype "bidirectional"))
    )
    (net (code "23") (name "Net-(49.9-Pad2)") (class "Default")
      (node (ref "49.9") (pin "2") (pinfunction "2_2") (pintype "passive"))
      (node (ref "LED2") (pin "C") (pinfunction "C_C") (pintype "passive"))
    )
    (net (code "24") (name "Net-(C16-Pad2)") (class "Default")
      (node (ref "C16") (pin "2") (pinfunction "2_2") (pintype "passive"))
      (node (ref "CTS1") (pin "1") (pinfunction "1_1") (pintype "passive"))
      (node (ref "U5") (pin "PH1") (pinfunction "PH1_PH1") (pintype "bidirectional"))
    )
    (net (code "25") (name "Net-(CTS1-2)") (class "Default")
      (node (ref "C19") (pin "2") (pinfunction "2_2") (pintype "passive"))
      (node (ref "CTS1") (pin "3") (pinfunction "2_3") (pintype "passive"))
      (node (ref "U5") (pin "PH0") (pinfunction "PH0_PH0") (pintype "bidirectional"))
    )
    (net (code "26") (name "Net-(J2-DIN{slash}~{CONFIG})") (class "Default")
      (node (ref "J2") (pin "3") (pinfunction "DIN/~{CONFIG}_3") (pintype "input"))
      (node (ref "U5") (pin "PB6") (pinfunction "PB6_PB6") (pintype "bidirectional"))
    )
    (net (code "27") (name "Net-(J2-DOUT)") (class "Default")
      (node (ref "J2") (pin "2") (pinfunction "DOUT_2") (pintype "output"))
      (node (ref "U5") (pin "PB7") (pinfunction "PB7_PB7") (pintype "bidirectional"))
    )
    (net (code "28") (name "Net-(JP2-Pad3)") (class "Default")
      (node (ref "JP2") (pin "3") (pinfunction "3_3") (pintype "passive"))
      (node (ref "U2") (pin "15") (pinfunction "OUTB_15") (pintype "bidirectional"))
      (node (ref "U2") (pin "16") (pinfunction "OUTB_16") (pintype "bidirectional"))
      (node (ref "U2") (pin "21") (pinfunction "OUTB_21") (pintype "bidirectional"))
      (node (ref "U2") (pin "OUTB") (pinfunction "OUTB_OUTB") (pintype "bidirectional"))
      (node (ref "U2") (pin "OUTB@1") (pinfunction "OUTB_OUTB@1") (pintype "bidirectional"))
    )
    (net (code "29") (name "Net-(JP2-Pad4)") (class "Default")
      (node (ref "JP2") (pin "4") (pinfunction "4_4") (pintype "passive"))
      (node (ref "U2") (pin "1") (pinfunction "OUTA_1") (pintype "bidirectional"))
      (node (ref "U2") (pin "25") (pinfunction "OUTA_25") (pintype "bidirectional"))
      (node (ref "U2") (pin "30") (pinfunction "OUTA_30") (pintype "bidirectional"))
      (node (ref "U2") (pin "OUTA") (pinfunction "OUTA_OUTA") (pintype "bidirectional"))
      (node (ref "U2") (pin "OUTA@1") (pinfunction "OUTA_OUTA@1") (pintype "bidirectional"))
    )
    (net (code "30") (name "Net-(JP14-Pad1)") (class "Default")
      (node (ref "JP14") (pin "1") (pinfunction "1_1") (pintype "passive"))
      (node (ref "U5") (pin "PB5") (pinfunction "PB5_PB5") (pintype "bidirectional"))
    )
    (net (code "31") (name "Net-(JP14-Pad2)") (class "Default")
      (node (ref "JP14") (pin "2") (pinfunction "2_2") (pintype "passive"))
      (node (ref "U5") (pin "PB4") (pinfunction "PB4_PB4") (pintype "bidirectional"))
    )
    (net (code "32") (name "Net-(JP14-Pad3)") (class "Default")
      (node (ref "JP14") (pin "3") (pinfunction "3_3") (pintype "passive"))
      (node (ref "U5") (pin "PD7") (pinfunction "PD7_PD7") (pintype "bidirectional"))
    )
    (net (code "33") (name "Net-(JP14-Pad4)") (class "Default")
      (node (ref "JP14") (pin "4") (pinfunction "4_4") (pintype "passive"))
      (node (ref "U5") (pin "PD6") (pinfunction "PD6_PD6") (pintype "bidirectional"))
    )
    (net (code "34") (name "Net-(JP15-Pad1)") (class "Default")
      (node (ref "JP15") (pin "1") (pinfunction "1_1") (pintype "passive"))
      (node (ref "U5") (pin "PD0") (pinfunction "PD0_PD0") (pintype "bidirectional"))
    )
    (net (code "35") (name "Net-(JP16-Pad1)") (class "Default")
      (node (ref "JP16") (pin "1") (pinfunction "1_1") (pintype "passive"))
      (node (ref "U5") (pin "PE3") (pinfunction "PE3_PE3") (pintype "bidirectional"))
    )
    (net (code "36") (name "Net-(JP16-Pad2)") (class "Default")
      (node (ref "JP16") (pin "2") (pinfunction "2_2") (pintype "passive"))
      (node (ref "U5") (pin "PE2") (pinfunction "PE2_PE2") (pintype "bidirectional"))
    )
    (net (code "37") (name "Net-(JP17-Pad1)") (class "Default")
      (node (ref "JP17") (pin "1") (pinfunction "1_1") (pintype "passive"))
      (node (ref "U5") (pin "PC3") (pinfunction "PC3_PC3") (pintype "bidirectional"))
    )
    (net (code "38") (name "Net-(JP17-Pad2)") (class "Default")
      (node (ref "JP17") (pin "2") (pinfunction "2_2") (pintype "passive"))
      (node (ref "U5") (pin "PC2") (pinfunction "PC2_PC2") (pintype "bidirectional"))
    )
    (net (code "39") (name "Net-(JP17-Pad3)") (class "Default")
      (node (ref "JP17") (pin "3") (pinfunction "3_3") (pintype "passive"))
      (node (ref "U5") (pin "PC1") (pinfunction "PC1_PC1") (pintype "bidirectional"))
    )
    (net (code "40") (name "Net-(JP17-Pad4)") (class "Default")
      (node (ref "JP17") (pin "4") (pinfunction "4_4") (pintype "passive"))
      (node (ref "U5") (pin "PC0") (pinfunction "PC0_PC0") (pintype "bidirectional"))
    )
    (net (code "41") (name "Net-(JP17-Pad5)") (class "Default")
      (node (ref "JP17") (pin "5") (pinfunction "5_5") (pintype "passive"))
      (node (ref "U5") (pin "PE6") (pinfunction "PE6_PE6") (pintype "bidirectional"))
    )
    (net (code "42") (name "Net-(JP17-Pad6)") (class "Default")
      (node (ref "JP17") (pin "6") (pinfunction "6_6") (pintype "passive"))
      (node (ref "U5") (pin "PE5") (pinfunction "PE5_PE5") (pintype "bidirectional"))
    )
    (net (code "43") (name "Net-(JP17-Pad7)") (class "Default")
      (node (ref "JP17") (pin "7") (pinfunction "7_7") (pintype "passive"))
      (node (ref "U5") (pin "PE4") (pinfunction "PE4_PE4") (pintype "bidirectional"))
    )
    (net (code "44") (name "Net-(JP18-Pad1)") (class "Default")
      (node (ref "JP18") (pin "1") (pinfunction "1_1") (pintype "passive"))
      (node (ref "U5") (pin "PA8") (pinfunction "PA8_PA8") (pintype "bidirectional"))
    )
    (net (code "45") (name "Net-(JP18-Pad2)") (class "Default")
      (node (ref "JP18") (pin "2") (pinfunction "2_2") (pintype "passive"))
      (node (ref "U5") (pin "PC7") (pinfunction "PC7_PC7") (pintype "bidirectional"))
    )
    (net (code "46") (name "Net-(JP18-Pad3)") (class "Default")
      (node (ref "JP18") (pin "3") (pinfunction "3_3") (pintype "passive"))
      (node (ref "U5") (pin "PC6") (pinfunction "PC6_PC6") (pintype "bidirectional"))
    )
    (net (code "47") (name "Net-(JP18-Pad4)") (class "Default")
      (node (ref "JP18") (pin "4") (pinfunction "4_4") (pintype "passive"))
      (node (ref "U5") (pin "PD15") (pinfunction "PD15_PD15") (pintype "bidirectional"))
    )
    (net (code "48") (name "Net-(JP18-Pad5)") (class "Default")
      (node (ref "JP18") (pin "5") (pinfunction "5_5") (pintype "passive"))
      (node (ref "U5") (pin "PD14") (pinfunction "PD14_PD14") (pintype "bidirectional"))
    )
    (net (code "49") (name "Net-(JP18-Pad6)") (class "Default")
      (node (ref "JP18") (pin "6") (pinfunction "6_6") (pintype "passive"))
      (node (ref "U5") (pin "PD13") (pinfunction "PD13_PD13") (pintype "bidirectional"))
    )
    (net (code "50") (name "Net-(JP18-Pad7)") (class "Default")
      (node (ref "JP18") (pin "7") (pinfunction "7_7") (pintype "passive"))
      (node (ref "U5") (pin "PD12") (pinfunction "PD12_PD12") (pintype "bidirectional"))
    )
    (net (code "51") (name "Net-(JP18-Pad8)") (class "Default")
      (node (ref "JP18") (pin "8") (pinfunction "8_8") (pintype "passive"))
      (node (ref "U5") (pin "PD11") (pinfunction "PD11_PD11") (pintype "bidirectional"))
    )
    (net (code "52") (name "Net-(JP19-Pad1)") (class "Default")
      (node (ref "JP19") (pin "1") (pinfunction "1_1") (pintype "passive"))
      (node (ref "U5") (pin "PE1") (pinfunction "PE1_PE1") (pintype "bidirectional"))
    )
    (net (code "53") (name "Net-(JP19-Pad2)") (class "Default")
      (node (ref "JP19") (pin "2") (pinfunction "2_2") (pintype "passive"))
      (node (ref "U5") (pin "PE0") (pinfunction "PE0_PE0") (pintype "bidirectional"))
    )
    (net (code "54") (name "Net-(JP20-Pad1)") (class "Default")
      (node (ref "JP20") (pin "1") (pinfunction "1_1") (pintype "passive"))
      (node (ref "U5") (pin "PD5") (pinfunction "PD5_PD5") (pintype "bidirectional"))
    )
    (net (code "55") (name "Net-(JP20-Pad2)") (class "Default")
      (node (ref "JP20") (pin "2") (pinfunction "2_2") (pintype "passive"))
      (node (ref "U5") (pin "PD4") (pinfunction "PD4_PD4") (pintype "bidirectional"))
    )
    (net (code "56") (name "Net-(JP20-Pad3)") (class "Default")
      (node (ref "JP20") (pin "3") (pinfunction "3_3") (pintype "passive"))
      (node (ref "U5") (pin "PD3") (pinfunction "PD3_PD3") (pintype "bidirectional"))
    )
    (net (code "57") (name "Net-(JP20-Pad4)") (class "Default")
      (node (ref "JP20") (pin "4") (pinfunction "4_4") (pintype "passive"))
      (node (ref "U5") (pin "PD1") (pinfunction "PD1_PD1") (pintype "bidirectional"))
    )
    (net (code "58") (name "Net-(JTAG1-Pad1)") (class "Default")
      (node (ref "JTAG1") (pin "1") (pinfunction "1_1") (pintype "passive"))
      (node (ref "R13") (pin "1") (pinfunction "1_1") (pintype "passive"))
    )
    (net (code "59") (name "Net-(LED1-PadC)") (class "Default")
      (node (ref "LED1") (pin "C") (pinfunction "C_C") (pintype "passive"))
      (node (ref "R11") (pin "2") (pinfunction "2_2") (pintype "passive"))
    )
    (net (code "60") (name "Net-(LED3-PadA)") (class "Default")
      (node (ref "LED3") (pin "A") (pinfunction "A_A") (pintype "passive"))
      (node (ref "U5") (pin "PC13") (pinfunction "PC13_PC13") (pintype "bidirectional"))
    )
    (net (code "61") (name "Net-(LED3-PadC)") (class "Default")
      (node (ref "LED3") (pin "C") (pinfunction "C_C") (pintype "passive"))
      (node (ref "R17") (pin "2") (pinfunction "2_2") (pintype "passive"))
    )
    (net (code "62") (name "Net-(LED4-PadA)") (class "Default")
      (node (ref "LED4") (pin "A") (pinfunction "A_A") (pintype "passive"))
      (node (ref "U5") (pin "PC14") (pinfunction "PC14_PC14") (pintype "bidirectional"))
    )
    (net (code "63") (name "Net-(LED4-PadC)") (class "Default")
      (node (ref "LED4") (pin "C") (pinfunction "C_C") (pintype "passive"))
      (node (ref "R18") (pin "2") (pinfunction "2_2") (pintype "passive"))
    )
    (net (code "64") (name "Net-(LED5-PadA)") (class "Default")
      (node (ref "LED5") (pin "A") (pinfunction "A_A") (pintype "passive"))
      (node (ref "U5") (pin "PC15") (pinfunction "PC15_PC15") (pintype "bidirectional"))
    )
    (net (code "65") (name "Net-(LED5-PadC)") (class "Default")
      (node (ref "LED5") (pin "C") (pinfunction "C_C") (pintype "passive"))
      (node (ref "R19") (pin "2") (pinfunction "2_2") (pintype "passive"))
    )
    (net (code "66") (name "Net-(Q1-D)") (class "Default")
      (node (ref "C5") (pin "+") (pinfunction "+_+") (pintype "passive"))
      (node (ref "C6") (pin "1") (pinfunction "1_1") (pintype "passive"))
      (node (ref "Q1") (pin "2") (pinfunction "D_2") (pintype "passive"))
      (node (ref "U2") (pin "13") (pinfunction "VCC_13") (pintype "power_in"))
      (node (ref "U2") (pin "23") (pinfunction "VCC_23") (pintype "power_in"))
      (node (ref "U2") (pin "3") (pinfunction "VCC_3") (pintype "power_in"))
      (node (ref "U2") (pin "VCC") (pinfunction "VCC_VCC") (pintype "power_in"))
      (node (ref "U2") (pin "VCC@1") (pinfunction "VCC_VCC@1") (pintype "power_in"))
    )
    (net (code "67") (name "Net-(Q1-G)") (class "Default")
      (node (ref "Q1") (pin "1") (pinfunction "G_1") (pintype "passive"))
      (node (ref "U2") (pin "11") (pinfunction "CP_11") (pintype "bidirectional"))
    )
    (net (code "68") (name "Net-(U2-CS)") (class "Default")
      (node (ref "R7") (pin "2") (pinfunction "2_2") (pintype "passive"))
      (node (ref "R9") (pin "2") (pinfunction "2_2") (pintype "passive"))
      (node (ref "U2") (pin "8") (pinfunction "CS_8") (pintype "bidirectional"))
    )
    (net (code "69") (name "Net-(U2-ENA)") (class "Default")
      (node (ref "R10") (pin "1") (pinfunction "1_1") (pintype "passive"))
      (node (ref "R2") (pin "2") (pinfunction "2_2") (pintype "passive"))
      (node (ref "U2") (pin "5") (pinfunction "ENA_5") (pintype "bidirectional"))
    )
    (net (code "70") (name "Net-(U2-ENB)") (class "Default")
      (node (ref "R3") (pin "2") (pinfunction "2_2") (pintype "passive"))
      (node (ref "R8") (pin "1") (pinfunction "1_1") (pintype "passive"))
      (node (ref "U2") (pin "9") (pinfunction "ENB_9") (pintype "bidirectional"))
    )
    (net (code "71") (name "Net-(U2-INA)") (class "Default")
      (node (ref "R4") (pin "2") (pinfunction "2_2") (pintype "passive"))
      (node (ref "U2") (pin "4") (pinfunction "INA_4") (pintype "bidirectional"))
    )
    (net (code "72") (name "Net-(U2-INB)") (class "Default")
      (node (ref "R5") (pin "2") (pinfunction "2_2") (pintype "passive"))
      (node (ref "U2") (pin "10") (pinfunction "INB_10") (pintype "bidirectional"))
    )
    (net (code "73") (name "Net-(U2-PWM)") (class "Default")
      (node (ref "R6") (pin "2") (pinfunction "2_2") (pintype "passive"))
      (node (ref "U2") (pin "7") (pinfunction "PWM_7") (pintype "bidirectional"))
    )
    (net (code "74") (name "Net-(U3-CPOUT)") (class "Default")
      (node (ref "C9") (pin "1") (pinfunction "1_1") (pintype "passive"))
      (node (ref "U3") (pin "20") (pinfunction "CPOUT_20") (pintype "bidirectional"))
    )
    (net (code "75") (name "Net-(U3-REGOUT)") (class "Default")
      (node (ref "C8") (pin "1") (pinfunction "1_1") (pintype "passive"))
      (node (ref "U3") (pin "10") (pinfunction "REGOUT_10") (pintype "bidirectional"))
    )
    (net (code "76") (name "Net-(U4-C1)") (class "Default")
      (node (ref "C11") (pin "1") (pinfunction "1_1") (pintype "passive"))
      (node (ref "U4") (pin "10") (pinfunction "C1_10") (pintype "bidirectional"))
    )
    (net (code "77") (name "Net-(U4-SETC)") (class "Default")
      (node (ref "C12") (pin "2") (pinfunction "2_2") (pintype "passive"))
      (node (ref "U4") (pin "12") (pinfunction "SETC_12") (pintype "bidirectional"))
    )
    (net (code "78") (name "Net-(U4-SETP)") (class "Default")
      (node (ref "C12") (pin "1") (pinfunction "1_1") (pintype "passive"))
      (node (ref "U4") (pin "8") (pinfunction "SETP_8") (pintype "bidirectional"))
    )
    (net (code "79") (name "RX1") (class "Default")
      (node (ref "JP8") (pin "2") (pinfunction "2_2") (pintype "passive"))
      (node (ref "U5") (pin "PA1") (pinfunction "PA1_PA1") (pintype "bidirectional"))
    )
    (net (code "80") (name "RX2") (class "Default")
      (node (ref "JP10") (pin "2") (pinfunction "2_2") (pintype "passive"))
      (node (ref "U5") (pin "PA3") (pinfunction "PA3_PA3") (pintype "bidirectional"))
    )
    (net (code "81") (name "RX3") (class "Default")
      (node (ref "JP12") (pin "2") (pinfunction "2_2") (pintype "passive"))
      (node (ref "U5") (pin "PB11") (pinfunction "PB11_PB11") (pintype "bidirectional"))
    )
    (net (code "82") (name "SCL1") (class "Default")
      (node (ref "JP11") (pin "2") (pinfunction "2_2") (pintype "passive"))
      (node (ref "JP9") (pin "2") (pinfunction "2_2") (pintype "passive"))
      (node (ref "R15") (pin "1") (pinfunction "1_1") (pintype "passive"))
      (node (ref "U4") (pin "1") (pinfunction "SCL_1") (pintype "bidirectional"))
      (node (ref "U5") (pin "PB8") (pinfunction "PB8_PB8") (pintype "bidirectional"))
    )
    (net (code "83") (name "SDA1") (class "Default")
      (node (ref "JP11") (pin "3") (pinfunction "3_3") (pintype "passive"))
      (node (ref "JP9") (pin "3") (pinfunction "3_3") (pintype "passive"))
      (node (ref "R14") (pin "1") (pinfunction "1_1") (pintype "passive"))
      (node (ref "U4") (pin "16") (pinfunction "SDA_16") (pintype "bidirectional"))
      (node (ref "U5") (pin "PB9") (pinfunction "PB9_PB9") (pintype "bidirectional"))
    )
    (net (code "84") (name "SDIO_CLK") (class "Default")
      (node (ref "J1") (pin "5") (pinfunction "SCLK_5") (pintype "input"))
      (node (ref "U5") (pin "PC12") (pinfunction "PC12_PC12") (pintype "bidirectional"))
    )
    (net (code "85") (name "SDIO_CMD") (class "Default")
      (node (ref "J1") (pin "3") (pinfunction "DATA_IN_3") (pintype "input"))
      (node (ref "U5") (pin "PD2") (pinfunction "PD2_PD2") (pintype "bidirectional"))
    )
    (net (code "86") (name "SDIO_D0") (class "Default")
      (node (ref "J1") (pin "7") (pinfunction "DATA_OUT_7") (pintype "output"))
      (node (ref "U5") (pin "PC8") (pinfunction "PC8_PC8") (pintype "bidirectional"))
    )
    (net (code "87") (name "SDIO_D1") (class "Default")
      (node (ref "J1") (pin "8") (pinfunction "DAT1_8") (pintype "bidirectional"))
      (node (ref "U5") (pin "PC9") (pinfunction "PC9_PC9") (pintype "bidirectional"))
    )
    (net (code "88") (name "SDIO_D2") (class "Default")
      (node (ref "J1") (pin "1") (pinfunction "DAT2_1") (pintype "bidirectional"))
      (node (ref "U5") (pin "PC10") (pinfunction "PC10_PC10") (pintype "bidirectional"))
    )
    (net (code "89") (name "SDIO_D3") (class "Default")
      (node (ref "J1") (pin "2") (pinfunction "CS_2") (pintype "input"))
      (node (ref "U5") (pin "PC11") (pinfunction "PC11_PC11") (pintype "bidirectional"))
    )
    (net (code "90") (name "SPI1_MISO") (class "Default")
      (node (ref "JP13") (pin "3") (pinfunction "3_3") (pintype "passive"))
      (node (ref "U5") (pin "PA6") (pinfunction "PA6_PA6") (pintype "bidirectional"))
    )
    (net (code "91") (name "SPI1_MOSI") (class "Default")
      (node (ref "JP13") (pin "2") (pinfunction "2_2") (pintype "passive"))
      (node (ref "U5") (pin "PA7") (pinfunction "PA7_PA7") (pintype "bidirectional"))
    )
    (net (code "92") (name "SPI1_NSS") (class "Default")
      (node (ref "JP13") (pin "5") (pinfunction "5_5") (pintype "passive"))
      (node (ref "U5") (pin "PA4") (pinfunction "PA4_PA4") (pintype "bidirectional"))
    )
    (net (code "93") (name "SPI1_SCK") (class "Default")
      (node (ref "JP13") (pin "4") (pinfunction "4_4") (pintype "passive"))
      (node (ref "U5") (pin "PA5") (pinfunction "PA5_PA5") (pintype "bidirectional"))
    )
    (net (code "94") (name "SPI2_CS") (class "Default")
      (node (ref "U3") (pin "8") (pinfunction "~{CS}_8") (pintype "bidirectional"))
      (node (ref "U5") (pin "PB12") (pinfunction "PB12_PB12") (pintype "bidirectional"))
    )
    (net (code "95") (name "SPI2_MISO") (class "Default")
      (node (ref "U3") (pin "9") (pinfunction "AD0/SDO_9") (pintype "bidirectional"))
      (node (ref "U5") (pin "PB14") (pinfunction "PB14_PB14") (pintype "bidirectional"))
    )
    (net (code "96") (name "SPI2_MOSI") (class "Default")
      (node (ref "U3") (pin "24") (pinfunction "SDA/SDI_24") (pintype "bidirectional"))
      (node (ref "U5") (pin "PB15") (pinfunction "PB15_PB15") (pintype "bidirectional"))
    )
    (net (code "97") (name "SPI2_SCK") (class "Default")
      (node (ref "U3") (pin "23") (pinfunction "SCL/SCLK_23") (pintype "bidirectional"))
      (node (ref "U5") (pin "PB13") (pinfunction "PB13_PB13") (pintype "bidirectional"))
    )
    (net (code "98") (name "TCK") (class "Default")
      (node (ref "JTAG1") (pin "4") (pinfunction "4_4") (pintype "passive"))
      (node (ref "U5") (pin "PA14") (pinfunction "PA14_PA14") (pintype "bidirectional"))
    )
    (net (code "99") (name "TDI") (class "Default")
      (node (ref "JTAG1") (pin "8") (pinfunction "8_8") (pintype "passive"))
      (node (ref "U5") (pin "PA15") (pinfunction "PA15_PA15") (pintype "bidirectional"))
    )
    (net (code "100") (name "TDO") (class "Default")
      (node (ref "JTAG1") (pin "6") (pinfunction "6_6") (pintype "passive"))
      (node (ref "U5") (pin "PB3") (pinfunction "PB3_PB3") (pintype "bidirectional"))
    )
    (net (code "101") (name "TMS") (class "Default")
      (node (ref "JTAG1") (pin "2") (pinfunction "2_2") (pintype "passive"))
      (node (ref "U5") (pin "PA13") (pinfunction "PA13_PA13") (pintype "bidirectional"))
    )
    (net (code "102") (name "TX1") (class "Default")
      (node (ref "JP8") (pin "3") (pinfunction "3_3") (pintype "passive"))
      (node (ref "U5") (pin "PA0") (pinfunction "PA0_PA0") (pintype "bidirectional"))
    )
    (net (code "103") (name "TX2") (class "Default")
      (node (ref "JP10") (pin "3") (pinfunction "3_3") (pintype "passive"))
      (node (ref "U5") (pin "PA2") (pinfunction "PA2_PA2") (pintype "bidirectional"))
    )
    (net (code "104") (name "TX3") (class "Default")
      (node (ref "JP12") (pin "3") (pinfunction "3_3") (pintype "passive"))
      (node (ref "U5") (pin "PB10") (pinfunction "PB10_PB10") (pintype "bidirectional"))
    )
    (net (code "105") (name "VIN") (class "Default")
      (node (ref "C1") (pin "1") (pinfunction "1_1") (pintype "passive"))
      (node (ref "C3") (pin "1") (pinfunction "1_1") (pintype "passive"))
      (node (ref "D1") (pin "C") (pinfunction "C_C") (pintype "passive"))
      (node (ref "JP1") (pin "2") (pinfunction "2_2") (pintype "passive"))
      (node (ref "JP2") (pin "1") (pinfunction "1_1") (pintype "passive"))
      (node (ref "LED1") (pin "A") (pinfunction "A_A") (pintype "passive"))
      (node (ref "Q1") (pin "3") (pinfunction "S_3") (pintype "passive"))
      (node (ref "U1") (pin "2") (pinfunction "VIN_2") (pintype "bidirectional"))
      (node (ref "U2") (pin "12") (pinfunction "VBAT_12") (pintype "power_in"))
    )
    (net (code "106") (name "unconnected-(J2-AD0{slash}DIO0-Pad20)") (class "Default")
      (node (ref "J2") (pin "20") (pinfunction "AD0/DIO0_20") (pintype "bidirectional"))
    )
    (net (code "107") (name "unconnected-(J2-AD1{slash}DIO1-Pad19)") (class "Default")
      (node (ref "J2") (pin "19") (pinfunction "AD1/DIO1_19") (pintype "bidirectional"))
    )
    (net (code "108") (name "unconnected-(J2-AD2{slash}DIO2-Pad18)") (class "Default")
      (node (ref "J2") (pin "18") (pinfunction "AD2/DIO2_18") (pintype "bidirectional"))
    )
    (net (code "109") (name "unconnected-(J2-ASSOC{slash}AD5{slash}DIO5-Pad15)") (class "Default")
      (node (ref "J2") (pin "15") (pinfunction "ASSOC/AD5/DIO5_15") (pintype "bidirectional"))
    )
    (net (code "110") (name "unconnected-(J2-CD{slash}DOUT_EN{slash}DO8-Pad4)") (class "Default")
      (node (ref "J2") (pin "4") (pinfunction "CD/DOUT_EN/DO8_4") (pintype "output"))
    )
    (net (code "111") (name "unconnected-(J2-COORD_SEL{slash}AD3{slash}DIO3-Pad17)") (class "Default")
      (node (ref "J2") (pin "17") (pinfunction "COORD_SEL/AD3/DIO3_17") (pintype "bidirectional"))
    )
    (net (code "112") (name "unconnected-(J2-ON{slash}~{SLEEP}-Pad13)") (class "Default")
      (node (ref "J2") (pin "13") (pinfunction "ON/~{SLEEP}_13") (pintype "output"))
    )
    (net (code "113") (name "unconnected-(J2-PWM0{slash}RSSI-Pad6)") (class "Default")
      (node (ref "J2") (pin "6") (pinfunction "PWM0/RSSI_6") (pintype "output"))
    )
    (net (code "114") (name "unconnected-(J2-RF_TX{slash}AD4{slash}DIO4-Pad11)") (class "Default")
      (node (ref "J2") (pin "11") (pinfunction "RF_TX/AD4/DIO4_11") (pintype "bidirectional"))
    )
    (net (code "115") (name "unconnected-(J2-~{CTS}{slash}DIO7-Pad12)") (class "Default")
      (node (ref "J2") (pin "12") (pinfunction "~{CTS}/DIO7_12") (pintype "bidirectional"))
    )
    (net (code "116") (name "unconnected-(J2-~{DTR}{slash}SLEEP_RQ{slash}DI8-Pad9)") (class "Default")
      (node (ref "J2") (pin "9") (pinfunction "~{DTR}/SLEEP_RQ/DI8_9") (pintype "bidirectional"))
    )
    (net (code "117") (name "unconnected-(J2-~{RTS}{slash}AD6{slash}DIO6-Pad16)") (class "Default")
      (node (ref "J2") (pin "16") (pinfunction "~{RTS}/AD6/DIO6_16") (pintype "bidirectional"))
    )
    (net (code "118") (name "unconnected-(JP4-Pad2)") (class "Default")
      (node (ref "JP4") (pin "2") (pinfunction "2_2") (pintype "passive"))
    )
    (net (code "119") (name "unconnected-(JP4-Pad3)") (class "Default")
      (node (ref "JP4") (pin "3") (pinfunction "3_3") (pintype "passive"))
    )
    (net (code "120") (name "unconnected-(JP5-Pad2)") (class "Default")
      (node (ref "JP5") (pin "2") (pinfunction "2_2") (pintype "passive"))
    )
    (net (code "121") (name "unconnected-(JP5-Pad3)") (class "Default")
      (node (ref "JP5") (pin "3") (pinfunction "3_3") (pintype "passive"))
    )
    (net (code "122") (name "unconnected-(JP6-Pad2)") (class "Default")
      (node (ref "JP6") (pin "2") (pinfunction "2_2") (pintype "passive"))
    )
    (net (code "123") (name "unconnected-(JP6-Pad3)") (class "Default")
      (node (ref "JP6") (pin "3") (pinfunction "3_3") (pintype "passive"))
    )
    (net (code "124") (name "unconnected-(JP7-Pad2)") (class "Default")
      (node (ref "JP7") (pin "2") (pinfunction "2_2") (pintype "passive"))
    )
    (net (code "125") (name "unconnected-(JP7-Pad3)") (class "Default")
      (node (ref "JP7") (pin "3") (pinfunction "3_3") (pintype "passive"))
    )
    (net (code "126") (name "unconnected-(JTAG1-Pad7)") (class "Default")
      (node (ref "JTAG1") (pin "7") (pinfunction "7_7") (pintype "passive"))
    )
    (net (code "127") (name "unconnected-(U1-ADJUST-Pad5)") (class "Default")
      (node (ref "U1") (pin "5") (pinfunction "ADJUST_5") (pintype "bidirectional"))
    )
    (net (code "128") (name "unconnected-(U1-ENABLE-Pad1)") (class "Default")
      (node (ref "U1") (pin "1") (pinfunction "ENABLE_1") (pintype "bidirectional"))
    )
    (net (code "129") (name "unconnected-(U2-NC-Pad2)") (class "Default")
      (node (ref "U2") (pin "2") (pinfunction "NC_2") (pintype "no_connect"))
    )
    (net (code "130") (name "unconnected-(U2-NC-Pad14)") (class "Default")
      (node (ref "U2") (pin "14") (pinfunction "NC_14") (pintype "no_connect"))
    )
    (net (code "131") (name "unconnected-(U2-NC-Pad17)") (class "Default")
      (node (ref "U2") (pin "17") (pinfunction "NC_17") (pintype "no_connect"))
    )
    (net (code "132") (name "unconnected-(U2-NC-Pad22)") (class "Default")
      (node (ref "U2") (pin "22") (pinfunction "NC_22") (pintype "no_connect"))
    )
    (net (code "133") (name "unconnected-(U2-NC-Pad24)") (class "Default")
      (node (ref "U2") (pin "24") (pinfunction "NC_24") (pintype "no_connect"))
    )
    (net (code "134") (name "unconnected-(U2-NC-Pad29)") (class "Default")
      (node (ref "U2") (pin "29") (pinfunction "NC_29") (pintype "no_connect"))
    )
    (net (code "135") (name "unconnected-(U3-AUX_CL-Pad7)") (class "Default")
      (node (ref "U3") (pin "7") (pinfunction "AUX_CL_7") (pintype "bidirectional"))
    )
    (net (code "136") (name "unconnected-(U3-AUX_DA-Pad6)") (class "Default")
      (node (ref "U3") (pin "6") (pinfunction "AUX_DA_6") (pintype "bidirectional"))
    )
    (net (code "137") (name "unconnected-(U4-DRDY-Pad15)") (class "Default")
      (node (ref "U4") (pin "15") (pinfunction "DRDY_15") (pintype "bidirectional"))
    )
    (net (code "138") (name "unconnected-(U4-NC-Pad3)") (class "Default")
      (node (ref "U4") (pin "3") (pinfunction "NC_3") (pintype "bidirectional"))
    )
    (net (code "139") (name "unconnected-(U4-NC-Pad5)") (class "Default")
      (node (ref "U4") (pin "5") (pinfunction "NC_5") (pintype "bidirectional"))
    )
    (net (code "140") (name "unconnected-(U4-NC-Pad6)") (class "Default")
      (node (ref "U4") (pin "6") (pinfunction "NC_6") (pintype "bidirectional"))
    )
    (net (code "141") (name "unconnected-(U4-NC-Pad7)") (class "Default")
      (node (ref "U4") (pin "7") (pinfunction "NC_7") (pintype "bidirectional"))
    )
    (net (code "142") (name "unconnected-(U4-NC-Pad14)") (class "Default")
      (node (ref "U4") (pin "14") (pinfunction "NC_14") (pintype "bidirectional"))
    )
    (net (code "143") (name "unconnected-(U5-PadBOOT0)") (class "Default")
      (node (ref "U5") (pin "BOOT0") (pinfunction "BOOT0_BOOT0") (pintype "bidirectional"))
    )
    (net (code "144") (name "unconnected-(U5-PadPC4)") (class "Default")
      (node (ref "U5") (pin "PC4") (pinfunction "PC4_PC4") (pintype "bidirectional"))
    )
    (net (code "145") (name "unconnected-(U5-PadPC5)") (class "Default")
      (node (ref "U5") (pin "PC5") (pinfunction "PC5_PC5") (pintype "bidirectional"))
    )
    (net (code "146") (name "unconnected-(U5-PadPDR_ON)") (class "Default")
      (node (ref "U5") (pin "PDR_ON") (pinfunction "PDR_ON_PDR_ON") (pintype "bidirectional"))
    )
    (net (code "147") (name "unconnected-(U5-PadVBAT)") (class "Default")
      (node (ref "U5") (pin "VBAT") (pinfunction "VBAT_VBAT") (pintype "bidirectional"))
    )
  )
)
